# pcbboard.net
KiCad netlist of a schematic drawn in EAGLE
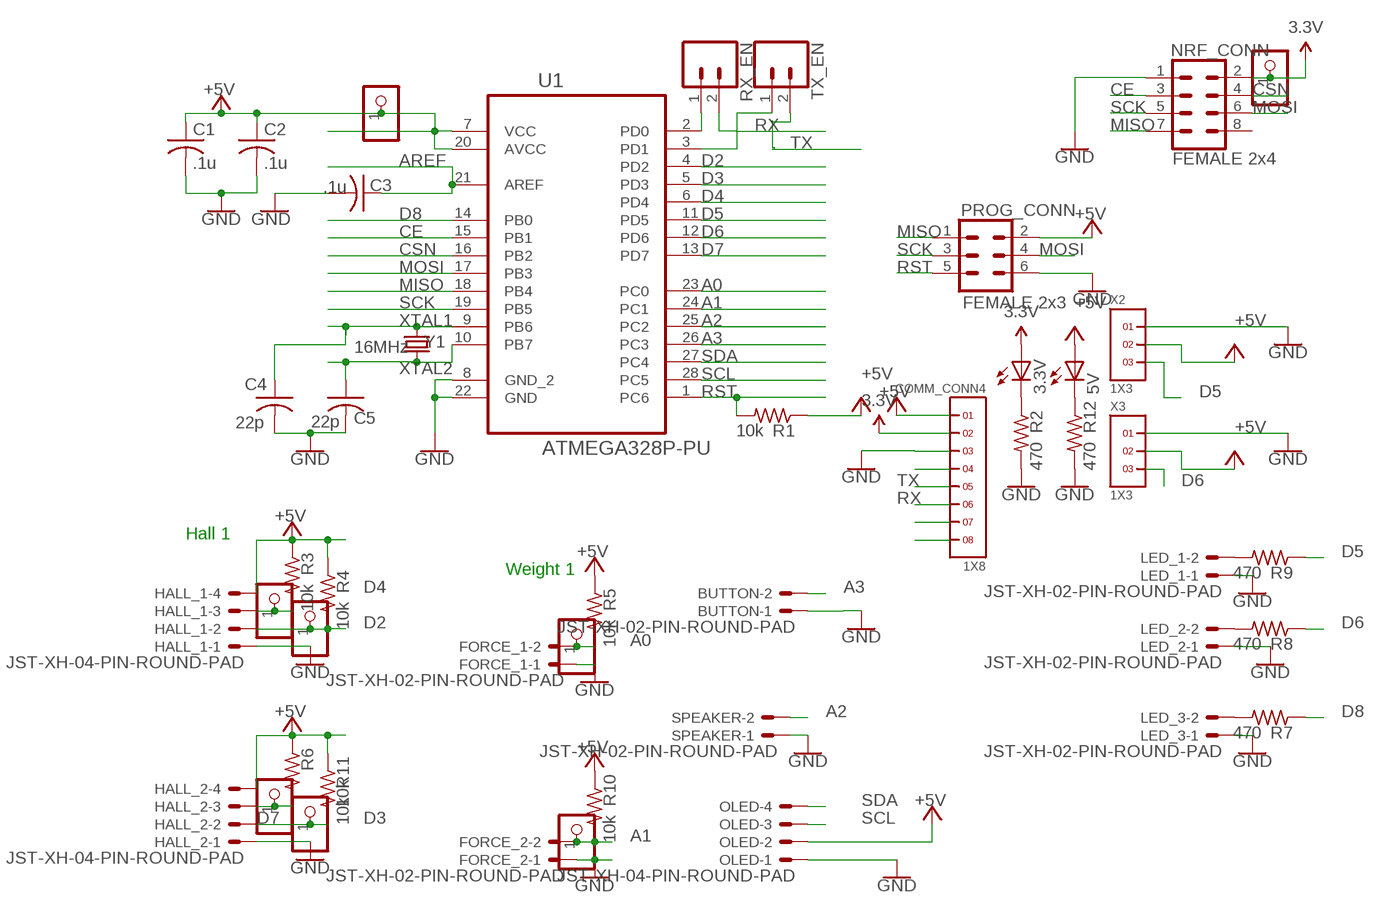
[diagram p0: schematic, sheet 1]

(export (version "E")
  (design (tool "Eeschema 10.0.6"))
  (components
    (comp (ref "3.3V")
      (value "LED3MM")
      (footprint "eagle-import:LED3MM")
      (libsource (lib "eagle-import") (part "LED3MM"))
    )
    (comp (ref "5V")
      (value "LED3MM")
      (footprint "eagle-import:LED3MM")
      (libsource (lib "eagle-import") (part "LED3MM"))
    )
    (comp (ref "BUTTON")
      (value "JST-XH-02-PIN-ROUND-PAD")
      (footprint "eagle-import:JST-XH-02-PACKAGE-ROUND-PAD")
      (libsource (lib "eagle-import") (part "JST-XH-02-PIN-ROUND-PAD"))
    )
    (comp (ref "C1")
      (value ".1u")
      (footprint "eagle-import:C0805")
      (libsource (lib "eagle-import") (part "C-USC0805"))
    )
    (comp (ref "C2")
      (value ".1u")
      (footprint "eagle-import:C0805")
      (libsource (lib "eagle-import") (part "C-USC0805"))
    )
    (comp (ref "C3")
      (value ".1u")
      (footprint "eagle-import:C0805")
      (libsource (lib "eagle-import") (part "C-USC0805"))
    )
    (comp (ref "C4")
      (value "22p")
      (footprint "eagle-import:C0805")
      (libsource (lib "eagle-import") (part "C-USC0805"))
    )
    (comp (ref "C5")
      (value "22p")
      (footprint "eagle-import:C0805")
      (libsource (lib "eagle-import") (part "C-USC0805"))
    )
    (comp (ref "COMM_CONN4")
      (value "1X8")
      (footprint "eagle-import:1X8")
      (libsource (lib "eagle-import") (part "1X8"))
    )
    (comp (ref "FORCE_1")
      (value "JST-XH-02-PIN-ROUND-PAD")
      (footprint "eagle-import:JST-XH-02-PACKAGE-ROUND-PAD")
      (libsource (lib "eagle-import") (part "JST-XH-02-PIN-ROUND-PAD"))
    )
    (comp (ref "FORCE_2")
      (value "JST-XH-02-PIN-ROUND-PAD")
      (footprint "eagle-import:JST-XH-02-PACKAGE-ROUND-PAD")
      (libsource (lib "eagle-import") (part "JST-XH-02-PIN-ROUND-PAD"))
    )
    (comp (ref "HALL_1")
      (value "JST-XH-04-PIN-ROUND-PAD")
      (footprint "eagle-import:JST-XH-04-PACKAGE-ROUND-PAD")
      (libsource (lib "eagle-import") (part "JST-XH-04-PIN-ROUND-PAD"))
    )
    (comp (ref "HALL_2")
      (value "JST-XH-04-PIN-ROUND-PAD")
      (footprint "eagle-import:JST-XH-04-PACKAGE-ROUND-PAD")
      (libsource (lib "eagle-import") (part "JST-XH-04-PIN-ROUND-PAD"))
    )
    (comp (ref "LED_1")
      (value "JST-XH-02-PIN-ROUND-PAD")
      (footprint "eagle-import:JST-XH-02-PACKAGE-ROUND-PAD")
      (libsource (lib "eagle-import") (part "JST-XH-02-PIN-ROUND-PAD"))
    )
    (comp (ref "LED_2")
      (value "JST-XH-02-PIN-ROUND-PAD")
      (footprint "eagle-import:JST-XH-02-PACKAGE-ROUND-PAD")
      (libsource (lib "eagle-import") (part "JST-XH-02-PIN-ROUND-PAD"))
    )
    (comp (ref "LED_3")
      (value "JST-XH-02-PIN-ROUND-PAD")
      (footprint "eagle-import:JST-XH-02-PACKAGE-ROUND-PAD")
      (libsource (lib "eagle-import") (part "JST-XH-02-PIN-ROUND-PAD"))
    )
    (comp (ref "NRF_CONN")
      (value "FEMALE 2x4")
      (footprint "eagle-import:2X4")
      (libsource (lib "eagle-import") (part "CONN_04X2"))
    )
    (comp (ref "OLED")
      (value "JST-XH-04-PIN-ROUND-PAD")
      (footprint "eagle-import:JST-XH-04-PACKAGE-ROUND-PAD")
      (libsource (lib "eagle-import") (part "JST-XH-04-PIN-ROUND-PAD"))
    )
    (comp (ref "PROG_CONN")
      (value "FEMALE 2x3")
      (footprint "eagle-import:2X3")
      (libsource (lib "eagle-import") (part "CONN_03X2FEMALE"))
    )
    (comp (ref "R1")
      (value "10k")
      (footprint "eagle-import:R0805")
      (libsource (lib "eagle-import") (part "R-US_R0805"))
    )
    (comp (ref "R2")
      (value "470")
      (footprint "eagle-import:R0805")
      (libsource (lib "eagle-import") (part "R-US_R0805"))
    )
    (comp (ref "R3")
      (value "10k")
      (footprint "eagle-import:R0805")
      (libsource (lib "eagle-import") (part "R-US_R0805"))
    )
    (comp (ref "R4")
      (value "10k")
      (footprint "eagle-import:R0805")
      (libsource (lib "eagle-import") (part "R-US_R0805"))
    )
    (comp (ref "R5")
      (value "10k")
      (footprint "eagle-import:R0805")
      (libsource (lib "eagle-import") (part "R-US_R0805"))
    )
    (comp (ref "R6")
      (value "10k")
      (footprint "eagle-import:R0805")
      (libsource (lib "eagle-import") (part "R-US_R0805"))
    )
    (comp (ref "R7")
      (value "470")
      (footprint "eagle-import:R0805")
      (libsource (lib "eagle-import") (part "R-US_R0805"))
    )
    (comp (ref "R8")
      (value "470")
      (footprint "eagle-import:R0805")
      (libsource (lib "eagle-import") (part "R-US_R0805"))
    )
    (comp (ref "R9")
      (value "470")
      (footprint "eagle-import:R0805")
      (libsource (lib "eagle-import") (part "R-US_R0805"))
    )
    (comp (ref "R10")
      (value "10k")
      (footprint "eagle-import:R0805")
      (libsource (lib "eagle-import") (part "R-US_R0805"))
    )
    (comp (ref "R11")
      (value "10k")
      (footprint "eagle-import:R0805")
      (libsource (lib "eagle-import") (part "R-US_R0805"))
    )
    (comp (ref "R12")
      (value "470")
      (footprint "eagle-import:R0805")
      (libsource (lib "eagle-import") (part "R-US_R0805"))
    )
    (comp (ref "RX_EN")
      (value "CONN_02")
      (footprint "eagle-import:1X02")
      (libsource (lib "eagle-import") (part "CONN_02"))
    )
    (comp (ref "SPEAKER")
      (value "JST-XH-02-PIN-ROUND-PAD")
      (footprint "eagle-import:JST-XH-02-PACKAGE-ROUND-PAD")
      (libsource (lib "eagle-import") (part "JST-XH-02-PIN-ROUND-PAD"))
    )
    (comp (ref "TP_3.3V")
      (value "PINHD-1X1")
      (footprint "eagle-import:1X01")
      (libsource (lib "eagle-import") (part "PINHD-1X1"))
    )
    (comp (ref "TP_5V")
      (value "PINHD-1X1")
      (footprint "eagle-import:1X01")
      (libsource (lib "eagle-import") (part "PINHD-1X1"))
    )
    (comp (ref "TP_F1")
      (value "PINHD-1X1")
      (footprint "eagle-import:1X01")
      (libsource (lib "eagle-import") (part "PINHD-1X1"))
    )
    (comp (ref "TP_F2")
      (value "PINHD-1X1")
      (footprint "eagle-import:1X01")
      (libsource (lib "eagle-import") (part "PINHD-1X1"))
    )
    (comp (ref "TP_H1-1")
      (value "PINHD-1X1")
      (footprint "eagle-import:1X01")
      (libsource (lib "eagle-import") (part "PINHD-1X1"))
    )
    (comp (ref "TP_H1-2")
      (value "PINHD-1X1")
      (footprint "eagle-import:1X01")
      (libsource (lib "eagle-import") (part "PINHD-1X1"))
    )
    (comp (ref "TP_H2-1")
      (value "PINHD-1X1")
      (footprint "eagle-import:1X01")
      (libsource (lib "eagle-import") (part "PINHD-1X1"))
    )
    (comp (ref "TP_H2-2")
      (value "PINHD-1X1")
      (footprint "eagle-import:1X01")
      (libsource (lib "eagle-import") (part "PINHD-1X1"))
    )
    (comp (ref "TX_EN")
      (value "CONN_02")
      (footprint "eagle-import:1X02")
      (libsource (lib "eagle-import") (part "CONN_02"))
    )
    (comp (ref "U1")
      (value "ATMEGA328P-PU")
      (footprint "eagle-import:DIP254P762X457-28")
      (libsource (lib "eagle-import") (part "ATMEGA328P-PU"))
    )
    (comp (ref "X2")
      (value "1X3")
      (footprint "eagle-import:1X3")
      (libsource (lib "eagle-import") (part "1X3"))
    )
    (comp (ref "X3")
      (value "1X3")
      (footprint "eagle-import:1X3")
      (libsource (lib "eagle-import") (part "1X3"))
    )
    (comp (ref "Y1")
      (value "16MHz")
      (footprint "eagle-import:CRYSTAL-SMD-5X3.2-4PAD")
      (libsource (lib "eagle-import") (part "CRYSTAL-8MHZSMD-5X3.2"))
    )
  )
  (nets
    (net (code "1") (name "+5V") (class "Default")
      (node (ref "5V") (pin "A") (pinfunction "A_A") (pintype "passive"))
      (node (ref "C1") (pin "1") (pinfunction "1_1") (pintype "passive"))
      (node (ref "C2") (pin "1") (pinfunction "1_1") (pintype "passive"))
      (node (ref "COMM_CONN4") (pin "1") (pinfunction "1_1") (pintype "bidirectional"))
      (node (ref "HALL_1") (pin "4") (pinfunction "S_4") (pintype "passive"))
      (node (ref "HALL_2") (pin "4") (pinfunction "S_4") (pintype "passive"))
      (node (ref "OLED") (pin "2") (pinfunction "S_2") (pintype "passive"))
      (node (ref "PROG_CONN") (pin "2") (pinfunction "2_2") (pintype "bidirectional"))
      (node (ref "R1") (pin "1") (pinfunction "1_1") (pintype "passive"))
      (node (ref "R10") (pin "1") (pinfunction "1_1") (pintype "passive"))
      (node (ref "R11") (pin "1") (pinfunction "1_1") (pintype "passive"))
      (node (ref "R3") (pin "1") (pinfunction "1_1") (pintype "passive"))
      (node (ref "R4") (pin "1") (pinfunction "1_1") (pintype "passive"))
      (node (ref "R5") (pin "1") (pinfunction "1_1") (pintype "passive"))
      (node (ref "R6") (pin "1") (pinfunction "1_1") (pintype "passive"))
      (node (ref "TP_5V") (pin "1") (pinfunction "1_1") (pintype "passive"))
      (node (ref "U1") (pin "20") (pinfunction "AVCC_20") (pintype "power_in"))
      (node (ref "U1") (pin "7") (pinfunction "VCC_7") (pintype "power_in"))
      (node (ref "X2") (pin "2") (pinfunction "2_2") (pintype "bidirectional"))
      (node (ref "X3") (pin "2") (pinfunction "2_2") (pintype "bidirectional"))
    )
    (net (code "2") (name "/A0") (class "Default")
      (node (ref "FORCE_1") (pin "2") (pinfunction "S_2") (pintype "passive"))
      (node (ref "R5") (pin "2") (pinfunction "2_2") (pintype "passive"))
      (node (ref "TP_F1") (pin "1") (pinfunction "1_1") (pintype "passive"))
      (node (ref "U1") (pin "23") (pinfunction "PC0_23") (pintype "bidirectional"))
    )
    (net (code "3") (name "/A1") (class "Default")
      (node (ref "FORCE_2") (pin "2") (pinfunction "S_2") (pintype "passive"))
      (node (ref "R10") (pin "2") (pinfunction "2_2") (pintype "passive"))
      (node (ref "TP_F2") (pin "1") (pinfunction "1_1") (pintype "passive"))
      (node (ref "U1") (pin "24") (pinfunction "PC1_24") (pintype "bidirectional"))
    )
    (net (code "4") (name "/A2") (class "Default")
      (node (ref "SPEAKER") (pin "2") (pinfunction "S_2") (pintype "passive"))
      (node (ref "U1") (pin "25") (pinfunction "PC2_25") (pintype "bidirectional"))
    )
    (net (code "5") (name "/A3") (class "Default")
      (node (ref "BUTTON") (pin "2") (pinfunction "S_2") (pintype "passive"))
      (node (ref "U1") (pin "26") (pinfunction "PC3_26") (pintype "bidirectional"))
    )
    (net (code "6") (name "/AREF") (class "Default")
      (node (ref "C3") (pin "1") (pinfunction "1_1") (pintype "passive"))
      (node (ref "U1") (pin "21") (pinfunction "AREF_21") (pintype "input"))
    )
    (net (code "7") (name "/CE") (class "Default")
      (node (ref "NRF_CONN") (pin "3") (pinfunction "3_3") (pintype "passive"))
      (node (ref "U1") (pin "15") (pinfunction "PB1_15") (pintype "bidirectional"))
    )
    (net (code "8") (name "/CSN") (class "Default")
      (node (ref "NRF_CONN") (pin "4") (pinfunction "4_4") (pintype "passive"))
      (node (ref "U1") (pin "16") (pinfunction "PB2_16") (pintype "bidirectional"))
    )
    (net (code "9") (name "/D2") (class "Default")
      (node (ref "HALL_1") (pin "2") (pinfunction "S_2") (pintype "passive"))
      (node (ref "R4") (pin "2") (pinfunction "2_2") (pintype "passive"))
      (node (ref "TP_H1-2") (pin "1") (pinfunction "1_1") (pintype "passive"))
      (node (ref "U1") (pin "4") (pinfunction "PD2_4") (pintype "bidirectional"))
    )
    (net (code "10") (name "/D3") (class "Default")
      (node (ref "HALL_2") (pin "2") (pinfunction "S_2") (pintype "passive"))
      (node (ref "R11") (pin "2") (pinfunction "2_2") (pintype "passive"))
      (node (ref "TP_H2-2") (pin "1") (pinfunction "1_1") (pintype "passive"))
      (node (ref "U1") (pin "5") (pinfunction "PD3_5") (pintype "bidirectional"))
    )
    (net (code "11") (name "/D4") (class "Default")
      (node (ref "HALL_1") (pin "3") (pinfunction "S_3") (pintype "passive"))
      (node (ref "R3") (pin "2") (pinfunction "2_2") (pintype "passive"))
      (node (ref "TP_H1-1") (pin "1") (pinfunction "1_1") (pintype "passive"))
      (node (ref "U1") (pin "6") (pinfunction "PD4_6") (pintype "bidirectional"))
    )
    (net (code "12") (name "/D5") (class "Default")
      (node (ref "R9") (pin "1") (pinfunction "1_1") (pintype "passive"))
      (node (ref "U1") (pin "11") (pinfunction "PD5_11") (pintype "bidirectional"))
      (node (ref "X2") (pin "3") (pinfunction "3_3") (pintype "bidirectional"))
    )
    (net (code "13") (name "/D6") (class "Default")
      (node (ref "R8") (pin "1") (pinfunction "1_1") (pintype "passive"))
      (node (ref "U1") (pin "12") (pinfunction "PD6_12") (pintype "bidirectional"))
      (node (ref "X3") (pin "3") (pinfunction "3_3") (pintype "bidirectional"))
    )
    (net (code "14") (name "/D7") (class "Default")
      (node (ref "HALL_2") (pin "3") (pinfunction "S_3") (pintype "passive"))
      (node (ref "R6") (pin "2") (pinfunction "2_2") (pintype "passive"))
      (node (ref "TP_H2-1") (pin "1") (pinfunction "1_1") (pintype "passive"))
      (node (ref "U1") (pin "13") (pinfunction "PD7_13") (pintype "bidirectional"))
    )
    (net (code "15") (name "/D8") (class "Default")
      (node (ref "R7") (pin "1") (pinfunction "1_1") (pintype "passive"))
      (node (ref "U1") (pin "14") (pinfunction "PB0_14") (pintype "bidirectional"))
    )
    (net (code "16") (name "/MISO") (class "Default")
      (node (ref "NRF_CONN") (pin "7") (pinfunction "7_7") (pintype "passive"))
      (node (ref "PROG_CONN") (pin "1") (pinfunction "1_1") (pintype "bidirectional"))
      (node (ref "U1") (pin "18") (pinfunction "PB4_18") (pintype "bidirectional"))
    )
    (net (code "17") (name "/MOSI") (class "Default")
      (node (ref "NRF_CONN") (pin "6") (pinfunction "6_6") (pintype "passive"))
      (node (ref "PROG_CONN") (pin "4") (pinfunction "4_4") (pintype "bidirectional"))
      (node (ref "U1") (pin "17") (pinfunction "PB3_17") (pintype "bidirectional"))
    )
    (net (code "18") (name "/RST") (class "Default")
      (node (ref "PROG_CONN") (pin "5") (pinfunction "5_5") (pintype "bidirectional"))
      (node (ref "R1") (pin "2") (pinfunction "2_2") (pintype "passive"))
      (node (ref "U1") (pin "1") (pinfunction "PC6_1") (pintype "bidirectional"))
    )
    (net (code "19") (name "/RX") (class "Default")
      (node (ref "COMM_CONN4") (pin "6") (pinfunction "6_6") (pintype "bidirectional"))
      (node (ref "RX_EN") (pin "2") (pinfunction "2_2") (pintype "passive"))
    )
    (net (code "20") (name "/SCK") (class "Default")
      (node (ref "NRF_CONN") (pin "5") (pinfunction "5_5") (pintype "passive"))
      (node (ref "PROG_CONN") (pin "3") (pinfunction "3_3") (pintype "bidirectional"))
      (node (ref "U1") (pin "19") (pinfunction "PB5_19") (pintype "bidirectional"))
    )
    (net (code "21") (name "/SCL") (class "Default")
      (node (ref "OLED") (pin "3") (pinfunction "S_3") (pintype "passive"))
      (node (ref "U1") (pin "28") (pinfunction "PC5_28") (pintype "bidirectional"))
    )
    (net (code "22") (name "/SDA") (class "Default")
      (node (ref "OLED") (pin "4") (pinfunction "S_4") (pintype "passive"))
      (node (ref "U1") (pin "27") (pinfunction "PC4_27") (pintype "bidirectional"))
    )
    (net (code "23") (name "/TX") (class "Default")
      (node (ref "COMM_CONN4") (pin "5") (pinfunction "5_5") (pintype "bidirectional"))
      (node (ref "TX_EN") (pin "2") (pinfunction "2_2") (pintype "passive"))
    )
    (net (code "24") (name "/XTAL1") (class "Default")
      (node (ref "C4") (pin "1") (pinfunction "1_1") (pintype "passive"))
      (node (ref "U1") (pin "9") (pinfunction "PB6_9") (pintype "bidirectional"))
      (node (ref "Y1") (pin "1") (pinfunction "1_1") (pintype "passive"))
    )
    (net (code "25") (name "/XTAL2") (class "Default")
      (node (ref "C5") (pin "1") (pinfunction "1_1") (pintype "passive"))
      (node (ref "U1") (pin "10") (pinfunction "PB7_10") (pintype "bidirectional"))
      (node (ref "Y1") (pin "3") (pinfunction "2_3") (pintype "passive"))
    )
    (net (code "26") (name "3.3V") (class "Default")
      (node (ref "3.3V") (pin "A") (pinfunction "A_A") (pintype "passive"))
      (node (ref "COMM_CONN4") (pin "2") (pinfunction "2_2") (pintype "bidirectional"))
      (node (ref "NRF_CONN") (pin "2") (pinfunction "2_2") (pintype "passive"))
      (node (ref "TP_3.3V") (pin "1") (pinfunction "1_1") (pintype "passive"))
    )
    (net (code "27") (name "GND") (class "Default")
      (node (ref "BUTTON") (pin "1") (pinfunction "S_1") (pintype "passive"))
      (node (ref "C1") (pin "2") (pinfunction "2_2") (pintype "passive"))
      (node (ref "C2") (pin "2") (pinfunction "2_2") (pintype "passive"))
      (node (ref "C3") (pin "2") (pinfunction "2_2") (pintype "passive"))
      (node (ref "C4") (pin "2") (pinfunction "2_2") (pintype "passive"))
      (node (ref "C5") (pin "2") (pinfunction "2_2") (pintype "passive"))
      (node (ref "COMM_CONN4") (pin "3") (pinfunction "3_3") (pintype "bidirectional"))
      (node (ref "FORCE_1") (pin "1") (pinfunction "S_1") (pintype "passive"))
      (node (ref "FORCE_2") (pin "1") (pinfunction "S_1") (pintype "passive"))
      (node (ref "HALL_1") (pin "1") (pinfunction "S_1") (pintype "passive"))
      (node (ref "HALL_2") (pin "1") (pinfunction "S_1") (pintype "passive"))
      (node (ref "LED_1") (pin "1") (pinfunction "S_1") (pintype "passive"))
      (node (ref "LED_2") (pin "1") (pinfunction "S_1") (pintype "passive"))
      (node (ref "LED_3") (pin "1") (pinfunction "S_1") (pintype "passive"))
      (node (ref "NRF_CONN") (pin "1") (pinfunction "1_1") (pintype "passive"))
      (node (ref "OLED") (pin "1") (pinfunction "S_1") (pintype "passive"))
      (node (ref "PROG_CONN") (pin "6") (pinfunction "6_6") (pintype "bidirectional"))
      (node (ref "R12") (pin "2") (pinfunction "2_2") (pintype "passive"))
      (node (ref "R2") (pin "2") (pinfunction "2_2") (pintype "passive"))
      (node (ref "SPEAKER") (pin "1") (pinfunction "S_1") (pintype "passive"))
      (node (ref "U1") (pin "22") (pinfunction "GND_22") (pintype "passive"))
      (node (ref "U1") (pin "8") (pinfunction "GND_2_8") (pintype "passive"))
      (node (ref "X2") (pin "1") (pinfunction "1_1") (pintype "bidirectional"))
      (node (ref "X3") (pin "1") (pinfunction "1_1") (pintype "bidirectional"))
    )
    (net (code "28") (name "Net-(3.3V-C)") (class "Default")
      (node (ref "3.3V") (pin "K") (pinfunction "C_K") (pintype "passive"))
      (node (ref "R2") (pin "1") (pinfunction "1_1") (pintype "passive"))
    )
    (net (code "29") (name "Net-(5V-C)") (class "Default")
      (node (ref "5V") (pin "K") (pinfunction "C_K") (pintype "passive"))
      (node (ref "R12") (pin "1") (pinfunction "1_1") (pintype "passive"))
    )
    (net (code "30") (name "Net-(LED_1B-S)") (class "Default")
      (node (ref "LED_1") (pin "2") (pinfunction "S_2") (pintype "passive"))
      (node (ref "R9") (pin "2") (pinfunction "2_2") (pintype "passive"))
    )
    (net (code "31") (name "Net-(LED_2B-S)") (class "Default")
      (node (ref "LED_2") (pin "2") (pinfunction "S_2") (pintype "passive"))
      (node (ref "R8") (pin "2") (pinfunction "2_2") (pintype "passive"))
    )
    (net (code "32") (name "Net-(LED_3B-S)") (class "Default")
      (node (ref "LED_3") (pin "2") (pinfunction "S_2") (pintype "passive"))
      (node (ref "R7") (pin "2") (pinfunction "2_2") (pintype "passive"))
    )
    (net (code "33") (name "Net-(U1-PD0)") (class "Default")
      (node (ref "RX_EN") (pin "1") (pinfunction "1_1") (pintype "passive"))
      (node (ref "U1") (pin "2") (pinfunction "PD0_2") (pintype "bidirectional"))
    )
    (net (code "34") (name "Net-(U1-PD1)") (class "Default")
      (node (ref "TX_EN") (pin "1") (pinfunction "1_1") (pintype "passive"))
      (node (ref "U1") (pin "3") (pinfunction "PD1_3") (pintype "bidirectional"))
    )
    (net (code "35") (name "unconnected-(COMM_CONN4-Pad4)") (class "Default")
      (node (ref "COMM_CONN4") (pin "4") (pinfunction "4_4") (pintype "bidirectional"))
    )
    (net (code "36") (name "unconnected-(COMM_CONN4-Pad7)") (class "Default")
      (node (ref "COMM_CONN4") (pin "7") (pinfunction "7_7") (pintype "bidirectional"))
    )
    (net (code "37") (name "unconnected-(COMM_CONN4-Pad8)") (class "Default")
      (node (ref "COMM_CONN4") (pin "8") (pinfunction "8_8") (pintype "bidirectional"))
    )
    (net (code "38") (name "unconnected-(NRF_CONN-Pad8)") (class "Default")
      (node (ref "NRF_CONN") (pin "8") (pinfunction "8_8") (pintype "passive"))
    )
  )
)
